# Jemuran.net
KiCad netlist of a schematic drawn in EAGLE
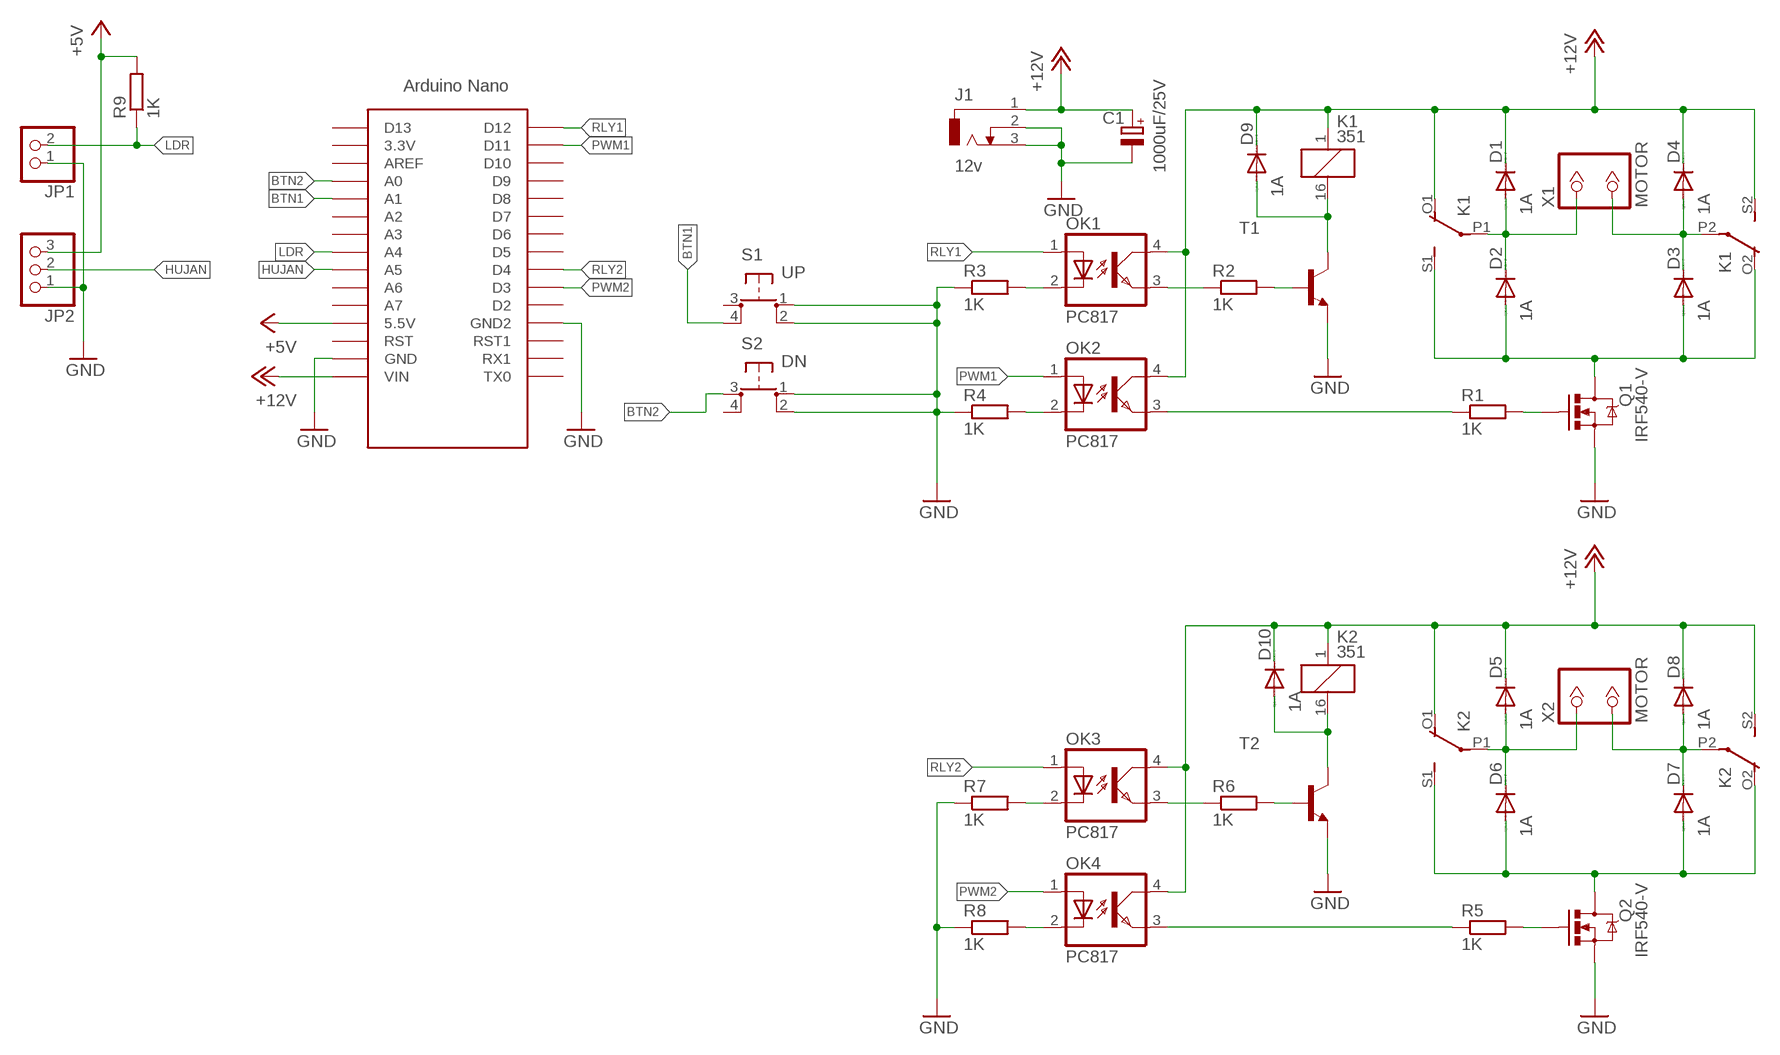
[diagram p0: schematic, sheet 1]

(export (version "E")
  (design (tool "Eeschema 10.0.6"))
  (components
    (comp (ref "C1")
      (value "1000uF/25V")
      (footprint "eagle-import:E3,5-10")
      (libsource (lib "eagle-import") (part "CPOL-EUE3.5-10"))
    )
    (comp (ref "D1")
      (value "1A")
      (footprint "eagle-import:D40-10")
      (libsource (lib "eagle-import") (part "DIODE-DIP-1A"))
    )
    (comp (ref "D2")
      (value "1A")
      (footprint "eagle-import:D40-10")
      (libsource (lib "eagle-import") (part "DIODE-DIP-1A"))
    )
    (comp (ref "D3")
      (value "1A")
      (footprint "eagle-import:D40-10")
      (libsource (lib "eagle-import") (part "DIODE-DIP-1A"))
    )
    (comp (ref "D4")
      (value "1A")
      (footprint "eagle-import:D40-10")
      (libsource (lib "eagle-import") (part "DIODE-DIP-1A"))
    )
    (comp (ref "D5")
      (value "1A")
      (footprint "eagle-import:D40-10")
      (libsource (lib "eagle-import") (part "DIODE-DIP-1A"))
    )
    (comp (ref "D6")
      (value "1A")
      (footprint "eagle-import:D40-10")
      (libsource (lib "eagle-import") (part "DIODE-DIP-1A"))
    )
    (comp (ref "D7")
      (value "1A")
      (footprint "eagle-import:D40-10")
      (libsource (lib "eagle-import") (part "DIODE-DIP-1A"))
    )
    (comp (ref "D8")
      (value "1A")
      (footprint "eagle-import:D40-10")
      (libsource (lib "eagle-import") (part "DIODE-DIP-1A"))
    )
    (comp (ref "D9")
      (value "1A")
      (footprint "eagle-import:D40-10")
      (libsource (lib "eagle-import") (part "DIODE-DIP-1A"))
    )
    (comp (ref "D10")
      (value "1A")
      (footprint "eagle-import:D40-10")
      (libsource (lib "eagle-import") (part "DIODE-DIP-1A"))
    )
    (comp (ref "J1")
      (value "12v")
      (footprint "eagle-import:JACK-PCB-ARDUINO")
      (libsource (lib "eagle-import") (part "JACK-PCB-ARDUINO"))
    )
    (comp (ref "JP1")
      (value "PINHD-1X2")
      (footprint "eagle-import:1X02")
      (libsource (lib "eagle-import") (part "PINHD-1X2"))
    )
    (comp (ref "JP2")
      (value "PINHD-1X3")
      (footprint "eagle-import:1X03")
      (libsource (lib "eagle-import") (part "PINHD-1X3"))
    )
    (comp (ref "K1")
      (value "351")
      (footprint "eagle-import:351")
      (libsource (lib "eagle-import") (part "351"))
    )
    (comp (ref "K2")
      (value "351")
      (footprint "eagle-import:351")
      (libsource (lib "eagle-import") (part "351"))
    )
    (comp (ref "OK1")
      (value "PC817")
      (footprint "eagle-import:DIL04")
      (fields (field (name "MPN") "PC817X4J000F"))
      (libsource (lib "eagle-import") (part "PC817"))
    )
    (comp (ref "OK2")
      (value "PC817")
      (footprint "eagle-import:DIL04")
      (fields (field (name "MPN") "PC817X4J000F"))
      (libsource (lib "eagle-import") (part "PC817"))
    )
    (comp (ref "OK3")
      (value "PC817")
      (footprint "eagle-import:DIL04")
      (fields (field (name "MPN") "PC817X4J000F"))
      (libsource (lib "eagle-import") (part "PC817"))
    )
    (comp (ref "OK4")
      (value "PC817")
      (footprint "eagle-import:DIL04")
      (fields (field (name "MPN") "PC817X4J000F"))
      (libsource (lib "eagle-import") (part "PC817"))
    )
    (comp (ref "Q1")
      (value "IRF540-V")
      (footprint "eagle-import:TO220V")
      (libsource (lib "eagle-import") (part "IRF540-V"))
    )
    (comp (ref "Q2")
      (value "IRF540-V")
      (footprint "eagle-import:TO220V")
      (libsource (lib "eagle-import") (part "IRF540-V"))
    )
    (comp (ref "R1")
      (value "1K")
      (footprint "eagle-import:0207_7")
      (libsource (lib "eagle-import") (part "R-EU_0207/7"))
    )
    (comp (ref "R2")
      (value "1K")
      (footprint "eagle-import:0207_7")
      (libsource (lib "eagle-import") (part "R-EU_0207/7"))
    )
    (comp (ref "R3")
      (value "1K")
      (footprint "eagle-import:0207_7")
      (libsource (lib "eagle-import") (part "R-EU_0207/7"))
    )
    (comp (ref "R4")
      (value "1K")
      (footprint "eagle-import:0207_7")
      (libsource (lib "eagle-import") (part "R-EU_0207/7"))
    )
    (comp (ref "R5")
      (value "1K")
      (footprint "eagle-import:0207_7")
      (libsource (lib "eagle-import") (part "R-EU_0207/7"))
    )
    (comp (ref "R6")
      (value "1K")
      (footprint "eagle-import:0207_7")
      (libsource (lib "eagle-import") (part "R-EU_0207/7"))
    )
    (comp (ref "R7")
      (value "1K")
      (footprint "eagle-import:0207_7")
      (libsource (lib "eagle-import") (part "R-EU_0207/7"))
    )
    (comp (ref "R8")
      (value "1K")
      (footprint "eagle-import:0207_7")
      (libsource (lib "eagle-import") (part "R-EU_0207/7"))
    )
    (comp (ref "R9")
      (value "1K")
      (footprint "eagle-import:0207_7")
      (libsource (lib "eagle-import") (part "R-EU_0207/7"))
    )
    (comp (ref "S1")
      (value "UP")
      (footprint "eagle-import:TACT-6X6MM-OCTAGON")
      (libsource (lib "eagle-import") (part "TACT-6X6OCT"))
    )
    (comp (ref "S2")
      (value "DN")
      (footprint "eagle-import:TACT-6X6MM-OCTAGON")
      (libsource (lib "eagle-import") (part "TACT-6X6OCT"))
    )
    (comp (ref "T1")
      (value "-NPN-TO92-EBC")
      (footprint "eagle-import:TO92-EBC")
      (libsource (lib "eagle-import") (part "-NPN-TO92-EBC"))
    )
    (comp (ref "T2")
      (value "-NPN-TO92-EBC")
      (footprint "eagle-import:TO92-EBC")
      (libsource (lib "eagle-import") (part "-NPN-TO92-EBC"))
    )
    (comp (ref "U$1")
      (value "NANO")
      (footprint "eagle-import:NANO")
      (libsource (lib "eagle-import") (part "NANO"))
    )
    (comp (ref "X1")
      (value "MOTOR")
      (footprint "eagle-import:KL2")
      (libsource (lib "eagle-import") (part "2PIN-SCREW"))
    )
    (comp (ref "X2")
      (value "MOTOR")
      (footprint "eagle-import:KL2")
      (libsource (lib "eagle-import") (part "2PIN-SCREW"))
    )
  )
  (nets
    (net (code "1") (name "+5V") (class "Default")
      (node (ref "JP2") (pin "3") (pinfunction "3_3") (pintype "passive"))
      (node (ref "R9") (pin "2") (pinfunction "2_2") (pintype "passive"))
      (node (ref "U$1") (pin "5V") (pinfunction "5.5V_5V") (pintype "bidirectional"))
    )
    (net (code "2") (name "+12V") (class "Default")
      (node (ref "C1") (pin "+") (pinfunction "+_+") (pintype "passive"))
      (node (ref "D1") (pin "C") (pinfunction "C_C") (pintype "passive"))
      (node (ref "D10") (pin "C") (pinfunction "C_C") (pintype "passive"))
      (node (ref "D4") (pin "C") (pinfunction "C_C") (pintype "passive"))
      (node (ref "D5") (pin "C") (pinfunction "C_C") (pintype "passive"))
      (node (ref "D8") (pin "C") (pinfunction "C_C") (pintype "passive"))
      (node (ref "D9") (pin "C") (pinfunction "C_C") (pintype "passive"))
      (node (ref "J1") (pin "1") (pinfunction "1_1") (pintype "passive"))
      (node (ref "K1") (pin "1") (pinfunction "1_1") (pintype "passive"))
      (node (ref "K1") (pin "O1") (pinfunction "O_O1") (pintype "passive"))
      (node (ref "K1") (pin "S2") (pinfunction "S_S2") (pintype "passive"))
      (node (ref "K2") (pin "1") (pinfunction "1_1") (pintype "passive"))
      (node (ref "K2") (pin "O1") (pinfunction "O_O1") (pintype "passive"))
      (node (ref "K2") (pin "S2") (pinfunction "S_S2") (pintype "passive"))
      (node (ref "OK1") (pin "4") (pinfunction "COL_4") (pintype "passive"))
      (node (ref "OK2") (pin "4") (pinfunction "COL_4") (pintype "passive"))
      (node (ref "OK3") (pin "4") (pinfunction "COL_4") (pintype "passive"))
      (node (ref "OK4") (pin "4") (pinfunction "COL_4") (pintype "passive"))
      (node (ref "U$1") (pin "VIN") (pinfunction "VIN_VIN") (pintype "bidirectional"))
    )
    (net (code "3") (name "BTN1") (class "Default")
      (node (ref "S1") (pin "4") (pinfunction "P1_4") (pintype "passive"))
      (node (ref "U$1") (pin "A1") (pinfunction "A1_A1") (pintype "bidirectional"))
    )
    (net (code "4") (name "BTN2") (class "Default")
      (node (ref "S2") (pin "3") (pinfunction "P_3") (pintype "passive"))
      (node (ref "U$1") (pin "A0") (pinfunction "A0_A0") (pintype "bidirectional"))
    )
    (net (code "5") (name "GND") (class "Default")
      (node (ref "C1") (pin "-") (pinfunction "-_-") (pintype "passive"))
      (node (ref "J1") (pin "2") (pinfunction "2_2") (pintype "passive"))
      (node (ref "J1") (pin "3") (pinfunction "3_3") (pintype "passive"))
      (node (ref "JP1") (pin "1") (pinfunction "1_1") (pintype "passive"))
      (node (ref "JP2") (pin "1") (pinfunction "1_1") (pintype "passive"))
      (node (ref "Q1") (pin "3") (pinfunction "S_3") (pintype "passive"))
      (node (ref "Q2") (pin "3") (pinfunction "S_3") (pintype "passive"))
      (node (ref "R3") (pin "1") (pinfunction "1_1") (pintype "passive"))
      (node (ref "R4") (pin "1") (pinfunction "1_1") (pintype "passive"))
      (node (ref "R7") (pin "1") (pinfunction "1_1") (pintype "passive"))
      (node (ref "R8") (pin "1") (pinfunction "1_1") (pintype "passive"))
      (node (ref "S1") (pin "1") (pinfunction "S_1") (pintype "passive"))
      (node (ref "S1") (pin "2") (pinfunction "S1_2") (pintype "passive"))
      (node (ref "S2") (pin "1") (pinfunction "S_1") (pintype "passive"))
      (node (ref "S2") (pin "2") (pinfunction "S1_2") (pintype "passive"))
      (node (ref "T1") (pin "E") (pinfunction "E_E") (pintype "passive"))
      (node (ref "T2") (pin "E") (pinfunction "E_E") (pintype "passive"))
      (node (ref "U$1") (pin "GND") (pinfunction "GND_GND") (pintype "bidirectional"))
      (node (ref "U$1") (pin "GND1") (pinfunction "GND2_GND1") (pintype "bidirectional"))
    )
    (net (code "6") (name "HUJAN") (class "Default")
      (node (ref "JP2") (pin "2") (pinfunction "2_2") (pintype "passive"))
      (node (ref "U$1") (pin "A5") (pinfunction "A5_A5") (pintype "bidirectional"))
    )
    (net (code "7") (name "LDR") (class "Default")
      (node (ref "JP1") (pin "2") (pinfunction "2_2") (pintype "passive"))
      (node (ref "R9") (pin "1") (pinfunction "1_1") (pintype "passive"))
      (node (ref "U$1") (pin "A4") (pinfunction "A4_A4") (pintype "bidirectional"))
    )
    (net (code "8") (name "Net-(K1A-2)") (class "Default")
      (node (ref "D9") (pin "A") (pinfunction "A_A") (pintype "passive"))
      (node (ref "K1") (pin "16") (pinfunction "2_16") (pintype "passive"))
      (node (ref "T1") (pin "C") (pinfunction "C_C") (pintype "passive"))
    )
    (net (code "9") (name "Net-(K1B-P)") (class "Default")
      (node (ref "D1") (pin "A") (pinfunction "A_A") (pintype "passive"))
      (node (ref "D2") (pin "C") (pinfunction "C_C") (pintype "passive"))
      (node (ref "K1") (pin "P1") (pinfunction "P_P1") (pintype "passive"))
      (node (ref "X1") (pin "1") (pinfunction "1_1") (pintype "bidirectional"))
    )
    (net (code "10") (name "Net-(K1B-S)") (class "Default")
      (node (ref "D2") (pin "A") (pinfunction "A_A") (pintype "passive"))
      (node (ref "D3") (pin "A") (pinfunction "A_A") (pintype "passive"))
      (node (ref "K1") (pin "O2") (pinfunction "O_O2") (pintype "passive"))
      (node (ref "K1") (pin "S1") (pinfunction "S_S1") (pintype "passive"))
      (node (ref "Q1") (pin "2") (pinfunction "D_2") (pintype "passive"))
    )
    (net (code "11") (name "Net-(K1C-P)") (class "Default")
      (node (ref "D3") (pin "C") (pinfunction "C_C") (pintype "passive"))
      (node (ref "D4") (pin "A") (pinfunction "A_A") (pintype "passive"))
      (node (ref "K1") (pin "P2") (pinfunction "P_P2") (pintype "passive"))
      (node (ref "X1") (pin "2") (pinfunction "2_2") (pintype "bidirectional"))
    )
    (net (code "12") (name "Net-(K2A-2)") (class "Default")
      (node (ref "D10") (pin "A") (pinfunction "A_A") (pintype "passive"))
      (node (ref "K2") (pin "16") (pinfunction "2_16") (pintype "passive"))
      (node (ref "T2") (pin "C") (pinfunction "C_C") (pintype "passive"))
    )
    (net (code "13") (name "Net-(K2B-P)") (class "Default")
      (node (ref "D5") (pin "A") (pinfunction "A_A") (pintype "passive"))
      (node (ref "D6") (pin "C") (pinfunction "C_C") (pintype "passive"))
      (node (ref "K2") (pin "P1") (pinfunction "P_P1") (pintype "passive"))
      (node (ref "X2") (pin "1") (pinfunction "1_1") (pintype "bidirectional"))
    )
    (net (code "14") (name "Net-(K2B-S)") (class "Default")
      (node (ref "D6") (pin "A") (pinfunction "A_A") (pintype "passive"))
      (node (ref "D7") (pin "A") (pinfunction "A_A") (pintype "passive"))
      (node (ref "K2") (pin "O2") (pinfunction "O_O2") (pintype "passive"))
      (node (ref "K2") (pin "S1") (pinfunction "S_S1") (pintype "passive"))
      (node (ref "Q2") (pin "2") (pinfunction "D_2") (pintype "passive"))
    )
    (net (code "15") (name "Net-(K2C-P)") (class "Default")
      (node (ref "D7") (pin "C") (pinfunction "C_C") (pintype "passive"))
      (node (ref "D8") (pin "A") (pinfunction "A_A") (pintype "passive"))
      (node (ref "K2") (pin "P2") (pinfunction "P_P2") (pintype "passive"))
      (node (ref "X2") (pin "2") (pinfunction "2_2") (pintype "bidirectional"))
    )
    (net (code "16") (name "Net-(OK1-C)") (class "Default")
      (node (ref "OK1") (pin "2") (pinfunction "C_2") (pintype "passive"))
      (node (ref "R3") (pin "2") (pinfunction "2_2") (pintype "passive"))
    )
    (net (code "17") (name "Net-(OK1-EMIT)") (class "Default")
      (node (ref "OK1") (pin "3") (pinfunction "EMIT_3") (pintype "passive"))
      (node (ref "R2") (pin "1") (pinfunction "1_1") (pintype "passive"))
    )
    (net (code "18") (name "Net-(OK2-C)") (class "Default")
      (node (ref "OK2") (pin "2") (pinfunction "C_2") (pintype "passive"))
      (node (ref "R4") (pin "2") (pinfunction "2_2") (pintype "passive"))
    )
    (net (code "19") (name "Net-(OK2-EMIT)") (class "Default")
      (node (ref "OK2") (pin "3") (pinfunction "EMIT_3") (pintype "passive"))
      (node (ref "R1") (pin "1") (pinfunction "1_1") (pintype "passive"))
    )
    (net (code "20") (name "Net-(OK3-C)") (class "Default")
      (node (ref "OK3") (pin "2") (pinfunction "C_2") (pintype "passive"))
      (node (ref "R7") (pin "2") (pinfunction "2_2") (pintype "passive"))
    )
    (net (code "21") (name "Net-(OK3-EMIT)") (class "Default")
      (node (ref "OK3") (pin "3") (pinfunction "EMIT_3") (pintype "passive"))
      (node (ref "R6") (pin "1") (pinfunction "1_1") (pintype "passive"))
    )
    (net (code "22") (name "Net-(OK4-C)") (class "Default")
      (node (ref "OK4") (pin "2") (pinfunction "C_2") (pintype "passive"))
      (node (ref "R8") (pin "2") (pinfunction "2_2") (pintype "passive"))
    )
    (net (code "23") (name "Net-(OK4-EMIT)") (class "Default")
      (node (ref "OK4") (pin "3") (pinfunction "EMIT_3") (pintype "passive"))
      (node (ref "R5") (pin "1") (pinfunction "1_1") (pintype "passive"))
    )
    (net (code "24") (name "Net-(Q1-G)") (class "Default")
      (node (ref "Q1") (pin "1") (pinfunction "G_1") (pintype "passive"))
      (node (ref "R1") (pin "2") (pinfunction "2_2") (pintype "passive"))
    )
    (net (code "25") (name "Net-(Q2-G)") (class "Default")
      (node (ref "Q2") (pin "1") (pinfunction "G_1") (pintype "passive"))
      (node (ref "R5") (pin "2") (pinfunction "2_2") (pintype "passive"))
    )
    (net (code "26") (name "Net-(R2-Pad2)") (class "Default")
      (node (ref "R2") (pin "2") (pinfunction "2_2") (pintype "passive"))
      (node (ref "T1") (pin "B") (pinfunction "B_B") (pintype "passive"))
    )
    (net (code "27") (name "Net-(R6-Pad2)") (class "Default")
      (node (ref "R6") (pin "2") (pinfunction "2_2") (pintype "passive"))
      (node (ref "T2") (pin "B") (pinfunction "B_B") (pintype "passive"))
    )
    (net (code "28") (name "PWM1") (class "Default")
      (node (ref "OK2") (pin "1") (pinfunction "A_1") (pintype "passive"))
      (node (ref "U$1") (pin "D11") (pinfunction "D11_D11") (pintype "bidirectional"))
    )
    (net (code "29") (name "PWM2") (class "Default")
      (node (ref "OK4") (pin "1") (pinfunction "A_1") (pintype "passive"))
      (node (ref "U$1") (pin "D3") (pinfunction "D3_D3") (pintype "bidirectional"))
    )
    (net (code "30") (name "RLY1") (class "Default")
      (node (ref "OK1") (pin "1") (pinfunction "A_1") (pintype "passive"))
      (node (ref "U$1") (pin "D12") (pinfunction "D12_D12") (pintype "bidirectional"))
    )
    (net (code "31") (name "RLY2") (class "Default")
      (node (ref "OK3") (pin "1") (pinfunction "A_1") (pintype "passive"))
      (node (ref "U$1") (pin "D4") (pinfunction "D4_D4") (pintype "bidirectional"))
    )
    (net (code "32") (name "unconnected-(S1-P-Pad3)") (class "Default")
      (node (ref "S1") (pin "3") (pinfunction "P_3") (pintype "passive"))
    )
    (net (code "33") (name "unconnected-(S2-P1-Pad4)") (class "Default")
      (node (ref "S2") (pin "4") (pinfunction "P1_4") (pintype "passive"))
    )
    (net (code "34") (name "unconnected-(U$1-Pad3.3V)") (class "Default")
      (node (ref "U$1") (pin "3.3V") (pinfunction "3.3V_3.3V") (pintype "bidirectional"))
    )
    (net (code "35") (name "unconnected-(U$1-PadA2)") (class "Default")
      (node (ref "U$1") (pin "A2") (pinfunction "A2_A2") (pintype "bidirectional"))
    )
    (net (code "36") (name "unconnected-(U$1-PadA3)") (class "Default")
      (node (ref "U$1") (pin "A3") (pinfunction "A3_A3") (pintype "bidirectional"))
    )
    (net (code "37") (name "unconnected-(U$1-PadA6)") (class "Default")
      (node (ref "U$1") (pin "A6") (pinfunction "A6_A6") (pintype "bidirectional"))
    )
    (net (code "38") (name "unconnected-(U$1-PadA7)") (class "Default")
      (node (ref "U$1") (pin "A7") (pinfunction "A7_A7") (pintype "bidirectional"))
    )
    (net (code "39") (name "unconnected-(U$1-PadAREF)") (class "Default")
      (node (ref "U$1") (pin "AREF") (pinfunction "AREF_AREF") (pintype "bidirectional"))
    )
    (net (code "40") (name "unconnected-(U$1-PadD2)") (class "Default")
      (node (ref "U$1") (pin "D2") (pinfunction "D2_D2") (pintype "bidirectional"))
    )
    (net (code "41") (name "unconnected-(U$1-PadD5)") (class "Default")
      (node (ref "U$1") (pin "D5") (pinfunction "D5_D5") (pintype "bidirectional"))
    )
    (net (code "42") (name "unconnected-(U$1-PadD6)") (class "Default")
      (node (ref "U$1") (pin "D6") (pinfunction "D6_D6") (pintype "bidirectional"))
    )
    (net (code "43") (name "unconnected-(U$1-PadD7)") (class "Default")
      (node (ref "U$1") (pin "D7") (pinfunction "D7_D7") (pintype "bidirectional"))
    )
    (net (code "44") (name "unconnected-(U$1-PadD8)") (class "Default")
      (node (ref "U$1") (pin "D8") (pinfunction "D8_D8") (pintype "bidirectional"))
    )
    (net (code "45") (name "unconnected-(U$1-PadD9)") (class "Default")
      (node (ref "U$1") (pin "D9") (pinfunction "D9_D9") (pintype "bidirectional"))
    )
    (net (code "46") (name "unconnected-(U$1-PadD10)") (class "Default")
      (node (ref "U$1") (pin "D10") (pinfunction "D10_D10") (pintype "bidirectional"))
    )
    (net (code "47") (name "unconnected-(U$1-PadD13)") (class "Default")
      (node (ref "U$1") (pin "D13") (pinfunction "D13_D13") (pintype "bidirectional"))
    )
    (net (code "48") (name "unconnected-(U$1-PadRST)") (class "Default")
      (node (ref "U$1") (pin "RST") (pinfunction "RST_RST") (pintype "bidirectional"))
    )
    (net (code "49") (name "unconnected-(U$1-PadRST1)") (class "Default")
      (node (ref "U$1") (pin "RST1") (pinfunction "RST1_RST1") (pintype "bidirectional"))
    )
    (net (code "50") (name "unconnected-(U$1-PadRX1)") (class "Default")
      (node (ref "U$1") (pin "RX1") (pinfunction "RX1_RX1") (pintype "bidirectional"))
    )
    (net (code "51") (name "unconnected-(U$1-PadTX0)") (class "Default")
      (node (ref "U$1") (pin "TX0") (pinfunction "TX0_TX0") (pintype "bidirectional"))
    )
  )
)
